# Main.net
KiCad netlist of a schematic drawn in Altium Designer
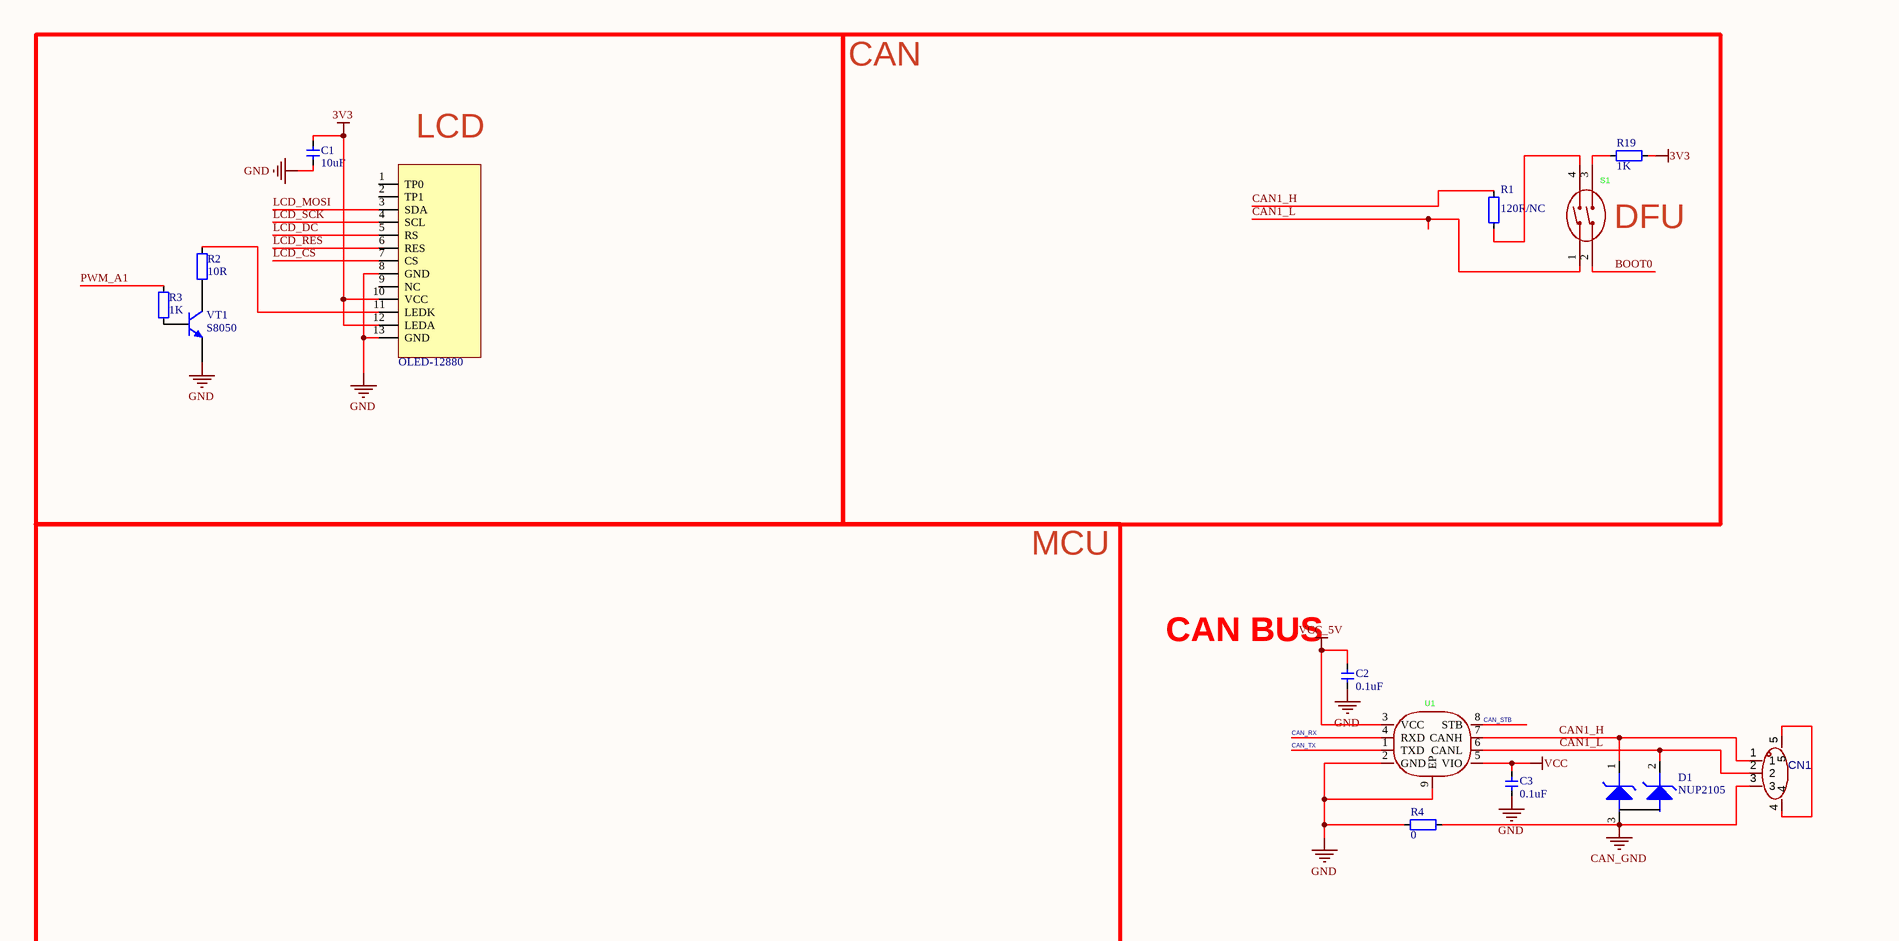
[diagram p0: Main.SchDoc, top]
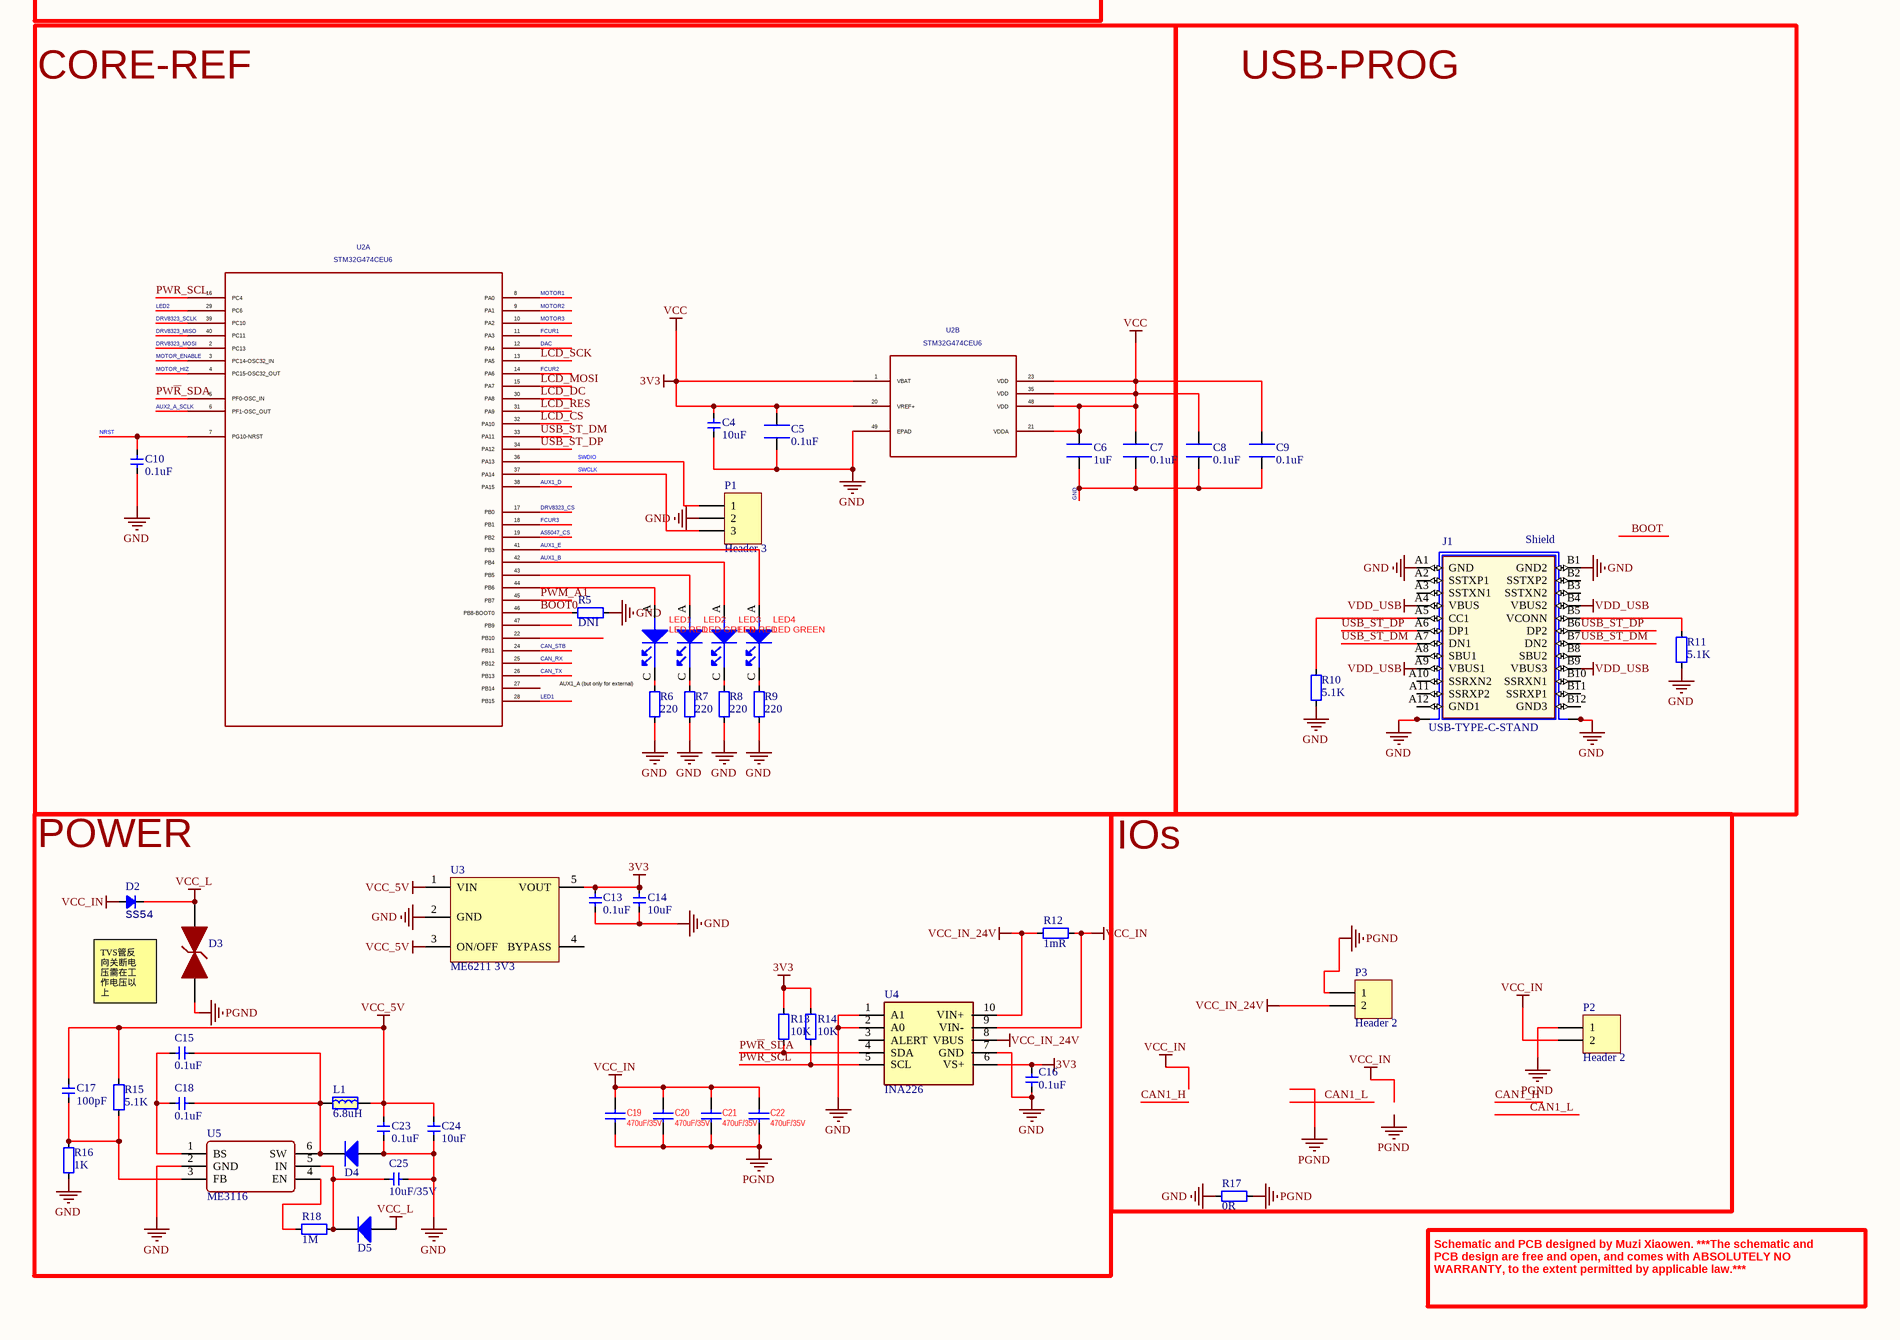
[diagram p1: Main.SchDoc, bottom]

(export (version "E")
  (design (tool "Eeschema 10.0.6"))
  (components
    (comp (ref "1")
      (value "OLED-12880")
      (footprint "OLED-12880")
      (libsource (lib "Schlib1") (part "LCD-ST7735"))
    )
    (comp (ref "C1")
      (value "10uF")
      (footprint "CAP_0402")
      (description "Capacitor")
      (libsource (lib "MyPcbLib") (part "电容-0402"))
    )
    (comp (ref "C2")
      (value "0.1uF")
      (footprint "CAP_0402")
      (description "Capacitor")
      (libsource (lib "MyPcbLib") (part "电容-0402"))
    )
    (comp (ref "C3")
      (value "0.1uF")
      (footprint "CAP_0402")
      (description "Capacitor")
      (libsource (lib "MyPcbLib") (part "电容-0402"))
    )
    (comp (ref "C4")
      (value "10uF")
      (footprint "CAP_0402")
      (description "Capacitor")
      (libsource (lib "MyPcbLib") (part "电容-0402"))
    )
    (comp (ref "C5")
      (value "0.1uF")
      (footprint "CAP_0402")
      (description "CAP CER 0.1UF 50V X7R 0603")
      (fields
        (field (name "MANUFACTURER") "Murata Electronics North America")
        (field (name "MANUFACTURER PART NUMBER") "GRM188R71H104KA93D")
      )
      (libsource (lib "CustomComponents") (part "GRM188R71H104KA93D"))
    )
    (comp (ref "C6")
      (value "1uF")
      (footprint "CAP_0402")
      (description "CAP CER 1UF 50V X7R 0603")
      (fields
        (field (name "MANUFACTURER") "Murata Electronics North America")
        (field (name "MANUFACTURER PART NUMBER") "GRM188R71H104KA93D")
      )
      (libsource (lib "CustomComponents") (part "GRM188R71H104KA93D"))
    )
    (comp (ref "C7")
      (value "0.1uF")
      (footprint "CAP_0402")
      (description "CAP CER 0.1UF 50V X7R 0603")
      (fields
        (field (name "MANUFACTURER") "Murata Electronics North America")
        (field (name "MANUFACTURER PART NUMBER") "GRM188R71H104KA93D")
      )
      (libsource (lib "CustomComponents") (part "GRM188R71H104KA93D"))
    )
    (comp (ref "C8")
      (value "0.1uF")
      (footprint "CAP_0402")
      (description "CAP CER 0.1UF 50V X7R 0603")
      (fields
        (field (name "MANUFACTURER") "Murata Electronics North America")
        (field (name "MANUFACTURER PART NUMBER") "GRM188R71H104KA93D")
      )
      (libsource (lib "CustomComponents") (part "GRM188R71H104KA93D"))
    )
    (comp (ref "C9")
      (value "0.1uF")
      (footprint "CAP_0402")
      (description "CAP CER 0.1UF 50V X7R 0603")
      (fields
        (field (name "MANUFACTURER") "Murata Electronics North America")
        (field (name "MANUFACTURER PART NUMBER") "GRM188R71H104KA93D")
      )
      (libsource (lib "CustomComponents") (part "GRM188R71H104KA93D"))
    )
    (comp (ref "C10")
      (value "0.1uF")
      (footprint "CAP_0402")
      (description "Capacitor")
      (libsource (lib "MyPcbLib") (part "电容-0402"))
    )
    (comp (ref "C13")
      (value "0.1uF")
      (footprint "CAP_0402")
      (description "Capacitor")
      (libsource (lib "MyPcbLib") (part "电容-0402"))
    )
    (comp (ref "C14")
      (value "10uF")
      (footprint "CAP_0402")
      (description "Capacitor")
      (libsource (lib "MyPcbLib") (part "电容-0402"))
    )
    (comp (ref "C15")
      (value "0.1uF")
      (footprint "CAP_0402")
      (description "Capacitor")
      (libsource (lib "MyPcbLib") (part "电容-0402"))
    )
    (comp (ref "C16")
      (value "0.1uF")
      (footprint "CAP_0402")
      (description "Capacitor")
      (libsource (lib "MyPcbLib") (part "电容-0402"))
    )
    (comp (ref "C17")
      (value "100pF")
      (footprint "CAP_0402")
      (description "Capacitor")
      (libsource (lib "MyPcbLib") (part "电容-0402"))
    )
    (comp (ref "C18")
      (value "0.1uF")
      (footprint "CAP_0402")
      (description "Capacitor")
      (libsource (lib "MyPcbLib") (part "电容-0402"))
    )
    (comp (ref "C19")
      (value "470uF/35V")
      (footprint "CAP-SMD_BD10.0-L10.3-W10.3-LS11.3-FD")
      (description "Capacitor, chip, ceramic")
      (fields (field (name "Comment") "220uF/25V"))
      (libsource (lib "OAKUSBFXS") (part "CAP"))
    )
    (comp (ref "C20")
      (value "470uF/35V")
      (footprint "CAP-SMD_BD10.0-L10.3-W10.3-LS11.3-FD")
      (description "Capacitor, chip, ceramic")
      (fields (field (name "Comment") "220uF/25V"))
      (libsource (lib "OAKUSBFXS") (part "CAP"))
    )
    (comp (ref "C21")
      (value "470uF/35V")
      (footprint "CAP-SMD_BD10.0-L10.3-W10.3-LS11.3-FD")
      (description "Capacitor, chip, ceramic")
      (fields (field (name "Comment") "220uF/25V"))
      (libsource (lib "OAKUSBFXS") (part "CAP"))
    )
    (comp (ref "C22")
      (value "470uF/35V")
      (footprint "CAP-SMD_BD10.0-L10.3-W10.3-LS11.3-FD")
      (description "Capacitor, chip, ceramic")
      (fields (field (name "Comment") "220uF/25V"))
      (libsource (lib "OAKUSBFXS") (part "CAP"))
    )
    (comp (ref "C23")
      (value "0.1uF")
      (footprint "CAP_0402")
      (description "Capacitor")
      (libsource (lib "MyPcbLib") (part "电容-0402"))
    )
    (comp (ref "C24")
      (value "10uF")
      (footprint "CAP_0402")
      (description "Capacitor")
      (libsource (lib "MyPcbLib") (part "电容-0402"))
    )
    (comp (ref "C25")
      (value "10uF/35V")
      (footprint "C0603")
      (description "Capacitor")
      (libsource (lib "MyPcbLib") (part "电容-0402"))
    )
    (comp (ref "CN1")
      (value "WAFER-GH1.25-3PLT-W1-P")
      (footprint "CONN-SMD_WAFER-GH1.25-3PLT-W1-P")
      (libsource (lib "altium-import") (part "root_0_WAFER-GH1.25-3PLT-W1-P_"))
    )
    (comp (ref "D1") (value "NUP2105") (footprint "SOT23-3") (libsource (lib "Schlib1") (part "NUP2105")))
    (comp (ref "D2")
      (value "SS54")
      (footprint "DO-214AC")
      (description "Diode")
      (libsource (lib "KitSprout") (part "Diode_SMA"))
    )
    (comp (ref "D3")
      (value "SMBJ28CA")
      (footprint "SMBJ-CA_MFG")
      (libsource (lib "MyPcbLib") (part "SMBJ28CA"))
    )
    (comp (ref "D4")
      (value "二极管-5819W")
      (footprint "SOD-323")
      (description "40V")
      (libsource (lib "MyPcbLib") (part "二极管-5819W"))
    )
    (comp (ref "D5")
      (value "二极管-5819W")
      (footprint "SOD-323")
      (description "40V")
      (libsource (lib "MyPcbLib") (part "二极管-5819W"))
    )
    (comp (ref "J1")
      (value "USB-TYPE-C-STAND")
      (footprint "USB-TYPE-C-STAND")
      (fields (field (name "MP") "632722110112") (field (name "MF") "Wurth Electronics"))
      (libsource (lib "MyPcbLib") (part "USB-TYPE-C-STAND"))
    )
    (comp (ref "L1") (value "6.8uH") (footprint "IND-201612") (libsource (lib "MyPcbLib") (part "电感-201612")))
    (comp (ref "LED1")
      (value "LED RED")
      (description "LED GRN SGL RA 25mA 4.1V SMD")
      (libsource (lib "*") (part "LED"))
    )
    (comp (ref "LED2")
      (value "LED GREEN")
      (description "LED GRN SGL RA 25mA 4.1V SMD")
      (libsource (lib "*") (part "LED"))
    )
    (comp (ref "LED3")
      (value "LED RED")
      (description "LED GRN SGL RA 25mA 4.1V SMD")
      (libsource (lib "*") (part "LED"))
    )
    (comp (ref "LED4")
      (value "LED GREEN")
      (description "LED GRN SGL RA 25mA 4.1V SMD")
      (libsource (lib "*") (part "LED"))
    )
    (comp (ref "P1")
      (value "Header 3")
      (footprint "HDR1X3")
      (description "Header, 3-Pin")
      (fields (field (name "PUBLISHER") "Altium Limited"))
      (libsource (lib "Miscellaneous Connectors") (part "Header 3"))
    )
    (comp (ref "P2")
      (value "Header 2")
      (footprint "CONN-TH_2P-P3.81_L7.4-W7.6")
      (description "Header, 2-Pin")
      (fields (field (name "PUBLISHER") "Altium Limited"))
      (libsource (lib "Miscellaneous Connectors") (part "Header 2"))
    )
    (comp (ref "P3")
      (value "Header 2")
      (footprint "CONN-TH_2P-P3.81_L7.4-W7.6")
      (description "Header, 2-Pin")
      (fields (field (name "PUBLISHER") "Altium Limited"))
      (libsource (lib "Miscellaneous Connectors") (part "Header 2"))
    )
    (comp (ref "R1")
      (value "120R/NC")
      (footprint "RES_0402_1")
      (description "Resistor")
      (libsource (lib "") (part "电阻-0402_2"))
    )
    (comp (ref "R2")
      (value "10R")
      (footprint "RES_0402_1")
      (description "Resistor")
      (libsource (lib "MyPcbLib") (part "电阻-0402"))
    )
    (comp (ref "R3")
      (value "1K")
      (footprint "RES_0402_1")
      (description "Resistor")
      (libsource (lib "") (part "电阻-0402_2"))
    )
    (comp (ref "R4")
      (value "0")
      (footprint "RES_0402")
      (description "Resistor")
      (libsource (lib "") (part "电阻-0402_1"))
    )
    (comp (ref "R5")
      (value "DNI")
      (footprint "RES_0402")
      (description "Resistor")
      (libsource (lib "") (part "电阻-0402_1"))
    )
    (comp (ref "R6")
      (value "220")
      (footprint "RES_0402_1")
      (description "Resistor")
      (libsource (lib "MyPcbLib") (part "电阻-0402"))
    )
    (comp (ref "R7")
      (value "220")
      (footprint "RES_0402_1")
      (description "Resistor")
      (libsource (lib "MyPcbLib") (part "电阻-0402"))
    )
    (comp (ref "R8")
      (value "220")
      (footprint "RES_0402_1")
      (description "Resistor")
      (libsource (lib "MyPcbLib") (part "电阻-0402"))
    )
    (comp (ref "R9")
      (value "220")
      (footprint "RES_0402_1")
      (description "Resistor")
      (libsource (lib "MyPcbLib") (part "电阻-0402"))
    )
    (comp (ref "R10")
      (value "5.1K")
      (footprint "RES_0402_1")
      (description "Resistor")
      (libsource (lib "") (part "电阻-0402_2"))
    )
    (comp (ref "R11")
      (value "5.1K")
      (footprint "RES_0402_1")
      (description "Resistor")
      (libsource (lib "") (part "电阻-0402_2"))
    )
    (comp (ref "R12")
      (value "1mR")
      (footprint "RES-SMD_L6.4-W3.2-R2512")
      (description "Resistor")
      (libsource (lib "MyPcbLib") (part "电阻-1206"))
    )
    (comp (ref "R13")
      (value "10K")
      (footprint "RES_0402_1")
      (description "Resistor")
      (libsource (lib "MyPcbLib") (part "电阻-0402"))
    )
    (comp (ref "R14")
      (value "10K")
      (footprint "RES_0402_1")
      (description "Resistor")
      (libsource (lib "MyPcbLib") (part "电阻-0402"))
    )
    (comp (ref "R15")
      (value "5.1K")
      (footprint "RES_0402_1")
      (description "Resistor")
      (libsource (lib "MyPcbLib") (part "电阻-0402"))
    )
    (comp (ref "R16")
      (value "1K")
      (footprint "RES_0402_1")
      (description "Resistor")
      (libsource (lib "MyPcbLib") (part "电阻-0402"))
    )
    (comp (ref "R17")
      (value "0R")
      (footprint "1206-RES")
      (description "Resistor")
      (libsource (lib "MyPcbLib") (part "电阻-1206"))
    )
    (comp (ref "R18")
      (value "1M")
      (footprint "RES_0402_1")
      (description "Resistor")
      (libsource (lib "") (part "电阻-0402_3"))
    )
    (comp (ref "R19")
      (value "1K")
      (footprint "RES_0402_1")
      (description "Resistor")
      (libsource (lib "") (part "电阻-0402_1"))
    )
    (comp (ref "S1")
      (value "ZX-1.27BM-2PSMD")
      (footprint "SW-SMD_2P-L5.4-W4.1-P1.27-LS8.4")
      (fields (field (name "MANUFACTURER") "Megastar(兆星)"))
      (libsource (lib "altium-import") (part "root_0_ZX-1.27BM-2PSMD_"))
    )
    (comp (ref "U1")
      (value "TCAN1057AVDRBRQ1")
      (footprint "SOIC8_2")
      (fields (field (name "MANUFACTURER") "SIT(芯力特)") (field (name "MANUFACTURER PART") "SIT1042ATK/3"))
      (libsource (lib "altium-import") (part "root_0_SIT1042ATK/3_"))
    )
    (comp (ref "U2")
      (value "STM32G474CEU6")
      (footprint "moteus:UFQFPN-48_7X7X0P55MM")
      (fields (field (name "MF") "ST") (field (name "Comment") "moteus_STM32G474CEU6"))
      (libsource (lib "altium-import") (part "root_0_moteus_STM32G474CEU6_"))
    )
    (comp (ref "U3")
      (value "ME6211 3V3")
      (footprint "SOT23-5")
      (description "LDO")
      (libsource (lib "MyPcbLib") (part "LP2992"))
    )
    (comp (ref "U4")
      (value "INA226")
      (footprint "MSOP-10_L3.0-W3.0-P0.50-LS5.0-BL")
      (fields
        (field (name "MOUSER PART NUMBER") "774-218-4LPSTJ")
        (field (name "MANUFACTURER_PART_NUMBER") "218-4LPSTJ")
      )
      (libsource (lib "Schlib1") (part "INA226"))
    )
    (comp (ref "U5")
      (value "ME3116")
      (footprint "SOT23-6")
      (description "DC-DC")
      (libsource (lib "MyPcbLib") (part "ME3116"))
    )
    (comp (ref "VT1")
      (value "S8050")
      (footprint "SMT_TRIODE_NPN")
      (description "Surface mount NPN transistor, package SOT-23")
      (libsource (lib "MyPcbLib") (part "SMT_TRIODE_NPN"))
    )
  )
  (nets
    (net (code "1") (name "/AS5047_CS") (class "Default")
      (node (ref "U2") (pin "19") (pinfunction "PB2_19") (pintype "passive"))
    )
    (net (code "2") (name "/AUX1_B") (class "Default")
      (node (ref "LED3") (pin "A") (pinfunction "ANODE_A") (pintype "passive"))
      (node (ref "U2") (pin "42") (pinfunction "PB4_42") (pintype "passive"))
    )
    (net (code "3") (name "/AUX1_D") (class "Default")
      (node (ref "U2") (pin "38") (pinfunction "PA15_38") (pintype "passive"))
    )
    (net (code "4") (name "/AUX1_E") (class "Default")
      (node (ref "LED4") (pin "A") (pinfunction "ANODE_A") (pintype "passive"))
      (node (ref "U2") (pin "41") (pinfunction "PB3_41") (pintype "passive"))
    )
    (net (code "5") (name "/AUX2_A_SCLK") (class "Default")
      (node (ref "U2") (pin "6") (pinfunction "PF1-OSC_OUT_6") (pintype "passive"))
    )
    (net (code "7") (name "/BOOT0") (class "Default")
      (node (ref "R5") (pin "1") (pinfunction "1_1") (pintype "passive"))
      (node (ref "S1") (pin "2") (pinfunction "2_2") (pintype "passive"))
      (node (ref "U2") (pin "46") (pinfunction "PB8-BOOT0_46") (pintype "passive"))
    )
    (net (code "8") (name "/CAN1_H") (class "Default")
      (node (ref "CN1") (pin "1") (pinfunction "1_1") (pintype "passive"))
      (node (ref "D1") (pin "1") (pinfunction "C_1") (pintype "passive"))
      (node (ref "R1") (pin "1") (pinfunction "1_1") (pintype "passive"))
      (node (ref "U1") (pin "7") (pinfunction "CANH_7") (pintype "passive"))
    )
    (net (code "9") (name "/CAN1_L") (class "Default")
      (node (ref "CN1") (pin "2") (pinfunction "2_2") (pintype "passive"))
      (node (ref "D1") (pin "2") (pinfunction "C_2") (pintype "passive"))
      (node (ref "S1") (pin "1") (pinfunction "1_1") (pintype "passive"))
      (node (ref "U1") (pin "6") (pinfunction "CANL_6") (pintype "passive"))
    )
    (net (code "10") (name "/CAN_RX") (class "Default")
      (node (ref "U1") (pin "4") (pinfunction "RXD_4") (pintype "passive"))
      (node (ref "U2") (pin "25") (pinfunction "PB12_25") (pintype "passive"))
    )
    (net (code "11") (name "/CAN_STB") (class "Default")
      (node (ref "U1") (pin "8") (pinfunction "STB_8") (pintype "passive"))
      (node (ref "U2") (pin "24") (pinfunction "PB11_24") (pintype "passive"))
    )
    (net (code "12") (name "/CAN_TX") (class "Default")
      (node (ref "U1") (pin "1") (pinfunction "TXD_1") (pintype "passive"))
      (node (ref "U2") (pin "26") (pinfunction "PB13_26") (pintype "passive"))
    )
    (net (code "13") (name "/DAC") (class "Default")
      (node (ref "U2") (pin "12") (pinfunction "PA4_12") (pintype "passive"))
    )
    (net (code "14") (name "/DRV8323_CS") (class "Default")
      (node (ref "U2") (pin "17") (pinfunction "PB0_17") (pintype "passive"))
    )
    (net (code "15") (name "/DRV8323_MISO") (class "Default")
      (node (ref "U2") (pin "40") (pinfunction "PC11_40") (pintype "passive"))
    )
    (net (code "16") (name "/DRV8323_MOSI") (class "Default")
      (node (ref "U2") (pin "2") (pinfunction "PC13_2") (pintype "passive"))
    )
    (net (code "17") (name "/DRV8323_SCLK") (class "Default")
      (node (ref "U2") (pin "39") (pinfunction "PC10_39") (pintype "passive"))
    )
    (net (code "18") (name "/FCUR1") (class "Default")
      (node (ref "U2") (pin "11") (pinfunction "PA3_11") (pintype "passive"))
    )
    (net (code "19") (name "/FCUR2") (class "Default")
      (node (ref "U2") (pin "14") (pinfunction "PA6_14") (pintype "passive"))
    )
    (net (code "20") (name "/FCUR3") (class "Default")
      (node (ref "U2") (pin "18") (pinfunction "PB1_18") (pintype "passive"))
    )
    (net (code "21") (name "/LCD_CS") (class "Default")
      (node (ref "1") (pin "7") (pinfunction "CS_7") (pintype "passive"))
      (node (ref "U2") (pin "32") (pinfunction "PA10_32") (pintype "passive"))
    )
    (net (code "22") (name "/LCD_DC") (class "Default")
      (node (ref "1") (pin "5") (pinfunction "RS_5") (pintype "passive"))
      (node (ref "U2") (pin "30") (pinfunction "PA8_30") (pintype "passive"))
    )
    (net (code "23") (name "/LCD_MOSI") (class "Default")
      (node (ref "1") (pin "3") (pinfunction "SDA_3") (pintype "passive"))
      (node (ref "U2") (pin "15") (pinfunction "PA7_15") (pintype "passive"))
    )
    (net (code "24") (name "/LCD_RES") (class "Default")
      (node (ref "1") (pin "6") (pinfunction "RES_6") (pintype "passive"))
      (node (ref "U2") (pin "31") (pinfunction "PA9_31") (pintype "passive"))
    )
    (net (code "25") (name "/LCD_SCK") (class "Default")
      (node (ref "1") (pin "4") (pinfunction "SCL_4") (pintype "passive"))
      (node (ref "U2") (pin "13") (pinfunction "PA5_13") (pintype "passive"))
    )
    (net (code "26") (name "/LED1") (class "Default")
      (node (ref "U2") (pin "28") (pinfunction "PB15_28") (pintype "passive"))
    )
    (net (code "27") (name "/LED2") (class "Default")
      (node (ref "U2") (pin "29") (pinfunction "PC6_29") (pintype "passive"))
    )
    (net (code "28") (name "/MOTOR1") (class "Default")
      (node (ref "U2") (pin "8") (pinfunction "PA0_8") (pintype "passive"))
    )
    (net (code "29") (name "/MOTOR2") (class "Default")
      (node (ref "U2") (pin "9") (pinfunction "PA1_9") (pintype "passive"))
    )
    (net (code "30") (name "/MOTOR3") (class "Default")
      (node (ref "U2") (pin "10") (pinfunction "PA2_10") (pintype "passive"))
    )
    (net (code "31") (name "/MOTOR_ENABLE") (class "Default")
      (node (ref "U2") (pin "3") (pinfunction "PC14-OSC32_IN_3") (pintype "passive"))
    )
    (net (code "32") (name "/MOTOR_HIZ") (class "Default")
      (node (ref "U2") (pin "4") (pinfunction "PC15-OSC32_OUT_4") (pintype "passive"))
    )
    (net (code "33") (name "/NRST") (class "Default")
      (node (ref "C10") (pin "2") (pinfunction "2_2") (pintype "passive"))
      (node (ref "U2") (pin "7") (pinfunction "PG10-NRST_7") (pintype "passive"))
    )
    (net (code "34") (name "/PWM_A1") (class "Default")
      (node (ref "R3") (pin "1") (pinfunction "1_1") (pintype "passive"))
      (node (ref "U2") (pin "45") (pinfunction "PB7_45") (pintype "passive"))
    )
    (net (code "35") (name "/PWR_SCL") (class "Default")
      (node (ref "R14") (pin "1") (pinfunction "1_1") (pintype "passive"))
      (node (ref "U2") (pin "16") (pinfunction "PC4_16") (pintype "passive"))
      (node (ref "U4") (pin "5") (pinfunction "SCL_5") (pintype "passive"))
    )
    (net (code "36") (name "/PW~{R}_SDA") (class "Default")
      (node (ref "R13") (pin "1") (pinfunction "1_1") (pintype "passive"))
      (node (ref "U2") (pin "5") (pinfunction "PF0-OSC_IN_5") (pintype "passive"))
      (node (ref "U4") (pin "4") (pinfunction "SDA_4") (pintype "passive"))
    )
    (net (code "37") (name "/SWCLK") (class "Default")
      (node (ref "P1") (pin "3") (pinfunction "3_3") (pintype "passive"))
      (node (ref "U2") (pin "37") (pinfunction "PA14_37") (pintype "passive"))
    )
    (net (code "38") (name "/SWDIO") (class "Default")
      (node (ref "P1") (pin "1") (pinfunction "1_1") (pintype "passive"))
      (node (ref "U2") (pin "36") (pinfunction "PA13_36") (pintype "passive"))
    )
    (net (code "39") (name "/USB_ST_DM") (class "Default")
      (node (ref "J1") (pin "A7") (pinfunction "DN1_A7") (pintype "bidirectional"))
      (node (ref "J1") (pin "B7") (pinfunction "DN2_B7") (pintype "bidirectional"))
      (node (ref "U2") (pin "33") (pinfunction "PA11_33") (pintype "passive"))
    )
    (net (code "40") (name "/USB_ST_DP") (class "Default")
      (node (ref "J1") (pin "A6") (pinfunction "DP1_A6") (pintype "bidirectional"))
      (node (ref "J1") (pin "B6") (pinfunction "DP2_B6") (pintype "bidirectional"))
      (node (ref "U2") (pin "34") (pinfunction "PA12_34") (pintype "passive"))
    )
    (net (code "41") (name "3V3") (class "Default")
      (node (ref "1") (pin "10") (pinfunction "VCC_10") (pintype "passive"))
      (node (ref "1") (pin "12") (pinfunction "LEDA_12") (pintype "passive"))
      (node (ref "C1") (pin "2") (pinfunction "2_2") (pintype "passive"))
      (node (ref "C13") (pin "2") (pinfunction "2_2") (pintype "passive"))
      (node (ref "C14") (pin "2") (pinfunction "2_2") (pintype "passive"))
      (node (ref "C16") (pin "2") (pinfunction "2_2") (pintype "passive"))
      (node (ref "C3") (pin "1") (pinfunction "1_1") (pintype "passive"))
      (node (ref "C4") (pin "2") (pinfunction "2_2") (pintype "passive"))
      (node (ref "C5") (pin "1") (pinfunction "1_1") (pintype "passive"))
      (node (ref "C6") (pin "1") (pinfunction "1_1") (pintype "passive"))
      (node (ref "C7") (pin "2") (pinfunction "2_2") (pintype "passive"))
      (node (ref "C8") (pin "1") (pinfunction "1_1") (pintype "passive"))
      (node (ref "C9") (pin "1") (pinfunction "1_1") (pintype "passive"))
      (node (ref "R13") (pin "2") (pinfunction "2_2") (pintype "passive"))
      (node (ref "R14") (pin "2") (pinfunction "2_2") (pintype "passive"))
      (node (ref "R19") (pin "2") (pinfunction "2_2") (pintype "passive"))
      (node (ref "U1") (pin "5") (pinfunction "VIO_5") (pintype "passive"))
      (node (ref "U2") (pin "1") (pinfunction "VBAT_1") (pintype "passive"))
      (node (ref "U2") (pin "20") (pinfunction "VREF+_20") (pintype "passive"))
      (node (ref "U2") (pin "21") (pinfunction "VDDA_21") (pintype "passive"))
      (node (ref "U2") (pin "23") (pinfunction "VDD_23") (pintype "passive"))
      (node (ref "U2") (pin "35") (pinfunction "VDD_35") (pintype "passive"))
      (node (ref "U2") (pin "48") (pinfunction "VDD_48") (pintype "passive"))
      (node (ref "U3") (pin "5") (pinfunction "VOUT_5") (pintype "passive"))
      (node (ref "U4") (pin "6") (pinfunction "VS+_6") (pintype "passive"))
    )
    (net (code "42") (name "CAN_GND") (class "Default")
      (node (ref "CN1") (pin "3") (pinfunction "3_3") (pintype "passive"))
      (node (ref "D1") (pin "3") (pinfunction "A_3") (pintype "passive"))
      (node (ref "R4") (pin "2") (pinfunction "2_2") (pintype "passive"))
    )
    (net (code "43") (name "GND") (class "Default")
      (node (ref "1") (pin "13") (pinfunction "GND_13") (pintype "passive"))
      (node (ref "1") (pin "8") (pinfunction "GND_8") (pintype "passive"))
      (node (ref "C1") (pin "1") (pinfunction "1_1") (pintype "passive"))
      (node (ref "C10") (pin "1") (pinfunction "1_1") (pintype "passive"))
      (node (ref "C13") (pin "1") (pinfunction "1_1") (pintype "passive"))
      (node (ref "C14") (pin "1") (pinfunction "1_1") (pintype "passive"))
      (node (ref "C16") (pin "1") (pinfunction "1_1") (pintype "passive"))
      (node (ref "C2") (pin "2") (pinfunction "2_2") (pintype "passive"))
      (node (ref "C23") (pin "1") (pinfunction "1_1") (pintype "passive"))
      (node (ref "C24") (pin "1") (pinfunction "1_1") (pintype "passive"))
      (node (ref "C25") (pin "2") (pinfunction "2_2") (pintype "passive"))
      (node (ref "C3") (pin "2") (pinfunction "2_2") (pintype "passive"))
      (node (ref "C4") (pin "1") (pinfunction "1_1") (pintype "passive"))
      (node (ref "C5") (pin "2") (pinfunction "2_2") (pintype "passive"))
      (node (ref "C6") (pin "2") (pinfunction "2_2") (pintype "passive"))
      (node (ref "C7") (pin "1") (pinfunction "1_1") (pintype "passive"))
      (node (ref "C8") (pin "2") (pinfunction "2_2") (pintype "passive"))
      (node (ref "C9") (pin "2") (pinfunction "2_2") (pintype "passive"))
      (node (ref "D4") (pin "1") (pinfunction "A_1") (pintype "passive"))
      (node (ref "J1") (pin "A1") (pinfunction "GND_A1") (pintype "bidirectional"))
      (node (ref "J1") (pin "B1") (pinfunction "GND2_B1") (pintype "bidirectional"))
      (node (ref "J1") (pin "S1") (pinfunction "SHIELD_S1") (pintype "bidirectional"))
      (node (ref "J1") (pin "S2") (pinfunction "SHIELD_S2") (pintype "bidirectional"))
      (node (ref "J1") (pin "S3") (pinfunction "SHIELD1_S3") (pintype "bidirectional"))
      (node (ref "J1") (pin "S4") (pinfunction "SHIELD1_S4") (pintype "bidirectional"))
      (node (ref "P1") (pin "2") (pinfunction "2_2") (pintype "passive"))
      (node (ref "R10") (pin "2") (pinfunction "2_2") (pintype "passive"))
      (node (ref "R11") (pin "2") (pinfunction "2_2") (pintype "passive"))
      (node (ref "R16") (pin "1") (pinfunction "1_1") (pintype "passive"))
      (node (ref "R17") (pin "1") (pinfunction "1_1") (pintype "passive"))
      (node (ref "R4") (pin "1") (pinfunction "1_1") (pintype "passive"))
      (node (ref "R5") (pin "2") (pinfunction "2_2") (pintype "passive"))
      (node (ref "R6") (pin "1") (pinfunction "1_1") (pintype "passive"))
      (node (ref "R7") (pin "1") (pinfunction "1_1") (pintype "passive"))
      (node (ref "R8") (pin "1") (pinfunction "1_1") (pintype "passive"))
      (node (ref "R9") (pin "1") (pinfunction "1_1") (pintype "passive"))
      (node (ref "U1") (pin "2") (pinfunction "GND_2") (pintype "passive"))
      (node (ref "U1") (pin "9") (pinfunction "EP_9") (pintype "passive"))
      (node (ref "U2") (pin "49") (pinfunction "EPAD_49") (pintype "passive"))
      (node (ref "U3") (pin "2") (pinfunction "GND_2") (pintype "passive"))
      (node (ref "U4") (pin "1") (pinfunction "A1_1") (pintype "passive"))
      (node (ref "U4") (pin "2") (pinfunction "A0_2") (pintype "passive"))
      (node (ref "U4") (pin "7") (pinfunction "GND_7") (pintype "passive"))
      (node (ref "U5") (pin "2") (pinfunction "GND_2") (pintype "passive"))
      (node (ref "VT1") (pin "2") (pinfunction "E_2") (pintype "passive"))
    )
    (net (code "44") (name "Net-(1-LEDK)") (class "Default")
      (node (ref "1") (pin "11") (pinfunction "LEDK_11") (pintype "passive"))
      (node (ref "R2") (pin "2") (pinfunction "2_2") (pintype "passive"))
    )
    (net (code "45") (name "Net-(CN1-Pad4)") (class "Default")
      (node (ref "CN1") (pin "4") (pinfunction "4_4") (pintype "passive"))
      (node (ref "CN1") (pin "5") (pinfunction "5_5") (pintype "passive"))
    )
    (net (code "46") (name "Net-(D4-K)") (class "Default")
      (node (ref "C15") (pin "1") (pinfunction "1_1") (pintype "passive"))
      (node (ref "C18") (pin "1") (pinfunction "1_1") (pintype "passive"))
      (node (ref "D4") (pin "2") (pinfunction "K_2") (pintype "passive"))
      (node (ref "L1") (pin "1") (pintype "passive"))
      (node (ref "U5") (pin "6") (pinfunction "SW_6") (pintype "passive"))
    )
    (net (code "47") (name "Net-(D5-K)") (class "Default")
      (node (ref "C25") (pin "1") (pinfunction "1_1") (pintype "passive"))
      (node (ref "D5") (pin "2") (pinfunction "K_2") (pintype "passive"))
      (node (ref "R18") (pin "1") (pinfunction "1_1") (pintype "passive"))
      (node (ref "U5") (pin "5") (pinfunction "IN_5") (pintype "passive"))
    )
    (net (code "48") (name "Net-(J1-CC1)") (class "Default")
      (node (ref "J1") (pin "A5") (pinfunction "CC1_A5") (pintype "bidirectional"))
      (node (ref "R10") (pin "1") (pinfunction "1_1") (pintype "passive"))
    )
    (net (code "49") (name "Net-(J1-VCONN)") (class "Default")
      (node (ref "J1") (pin "B5") (pinfunction "VCONN_B5") (pintype "bidirectional"))
      (node (ref "R11") (pin "1") (pinfunction "1_1") (pintype "passive"))
    )
    (net (code "50") (name "Net-(LED1-ANODE)") (class "Default")
      (node (ref "LED1") (pin "A") (pinfunction "ANODE_A") (pintype "passive"))
      (node (ref "U2") (pin "44") (pinfunction "PB6_44") (pintype "passive"))
    )
    (net (code "51") (name "Net-(LED1-CATHODE)") (class "Default")
      (node (ref "LED1") (pin "C") (pinfunction "CATHODE_C") (pintype "passive"))
      (node (ref "R6") (pin "2") (pinfunction "2_2") (pintype "passive"))
    )
    (net (code "52") (name "Net-(LED2-ANODE)") (class "Default")
      (node (ref "LED2") (pin "A") (pinfunction "ANODE_A") (pintype "passive"))
      (node (ref "U2") (pin "43") (pinfunction "PB5_43") (pintype "passive"))
    )
    (net (code "53") (name "Net-(LED2-CATHODE)") (class "Default")
      (node (ref "LED2") (pin "C") (pinfunction "CATHODE_C") (pintype "passive"))
      (node (ref "R7") (pin "2") (pinfunction "2_2") (pintype "passive"))
    )
    (net (code "54") (name "Net-(LED3-CATHODE)") (class "Default")
      (node (ref "LED3") (pin "C") (pinfunction "CATHODE_C") (pintype "passive"))
      (node (ref "R8") (pin "2") (pinfunction "2_2") (pintype "passive"))
    )
    (net (code "55") (name "Net-(LED4-CATHODE)") (class "Default")
      (node (ref "LED4") (pin "C") (pinfunction "CATHODE_C") (pintype "passive"))
      (node (ref "R9") (pin "2") (pinfunction "2_2") (pintype "passive"))
    )
    (net (code "56") (name "Net-(R1-Pad2)") (class "Default")
      (node (ref "R1") (pin "2") (pinfunction "2_2") (pintype "passive"))
      (node (ref "S1") (pin "4") (pinfunction "4_4") (pintype "passive"))
    )
    (net (code "57") (name "Net-(R19-Pad1)") (class "Default")
      (node (ref "R19") (pin "1") (pinfunction "1_1") (pintype "passive"))
      (node (ref "S1") (pin "3") (pinfunction "3_3") (pintype "passive"))
    )
    (net (code "58") (name "Net-(U5-BS)") (class "Default")
      (node (ref "C15") (pin "2") (pinfunction "2_2") (pintype "passive"))
      (node (ref "C18") (pin "2") (pinfunction "2_2") (pintype "passive"))
      (node (ref "U5") (pin "1") (pinfunction "BS_1") (pintype "passive"))
    )
    (net (code "59") (name "Net-(U5-EN)") (class "Default")
      (node (ref "R18") (pin "2") (pinfunction "2_2") (pintype "passive"))
      (node (ref "U5") (pin "4") (pinfunction "EN_4") (pintype "passive"))
    )
    (net (code "60") (name "Net-(U5-FB)") (class "Default")
      (node (ref "C17") (pin "2") (pinfunction "2_2") (pintype "passive"))
      (node (ref "R15") (pin "1") (pinfunction "1_1") (pintype "passive"))
      (node (ref "R16") (pin "2") (pinfunction "2_2") (pintype "passive"))
      (node (ref "U5") (pin "3") (pinfunction "FB_3") (pintype "passive"))
    )
    (net (code "61") (name "Net-(VT1-B)") (class "Default")
      (node (ref "R3") (pin "2") (pinfunction "2_2") (pintype "passive"))
      (node (ref "VT1") (pin "1") (pinfunction "B_1") (pintype "passive"))
    )
    (net (code "62") (name "Net-(VT1-C)") (class "Default")
      (node (ref "R2") (pin "1") (pinfunction "1_1") (pintype "passive"))
      (node (ref "VT1") (pin "3") (pinfunction "C_3") (pintype "passive"))
    )
    (net (code "63") (name "PGND") (class "Default")
      (node (ref "C19") (pin "2") (pinfunction "2_2") (pintype "passive"))
      (node (ref "C20") (pin "2") (pinfunction "2_2") (pintype "passive"))
      (node (ref "C21") (pin "2") (pinfunction "2_2") (pintype "passive"))
      (node (ref "C22") (pin "2") (pinfunction "2_2") (pintype "passive"))
      (node (ref "D3") (pin "1") (pinfunction "1_1") (pintype "passive"))
      (node (ref "P2") (pin "1") (pinfunction "1_1") (pintype "passive"))
      (node (ref "P3") (pin "1") (pinfunction "1_1") (pintype "passive"))
      (node (ref "R17") (pin "2") (pinfunction "2_2") (pintype "passive"))
    )
    (net (code "64") (name "VCC_5V") (class "Default")
      (node (ref "C17") (pin "1") (pinfunction "1_1") (pintype "passive"))
      (node (ref "C2") (pin "1") (pinfunction "1_1") (pintype "passive"))
      (node (ref "C23") (pin "2") (pinfunction "2_2") (pintype "passive"))
      (node (ref "C24") (pin "2") (pinfunction "2_2") (pintype "passive"))
      (node (ref "L1") (pin "2") (pinfunction "2_2") (pintype "passive"))
      (node (ref "R15") (pin "2") (pinfunction "2_2") (pintype "passive"))
      (node (ref "U1") (pin "3") (pinfunction "VCC_3") (pintype "passive"))
      (node (ref "U3") (pin "1") (pinfunction "VIN_1") (pintype "passive"))
      (node (ref "U3") (pin "3") (pinfunction "ON/OFF_3") (pintype "passive"))
    )
    (net (code "65") (name "VCC_IN") (class "Default")
      (node (ref "C19") (pin "1") (pinfunction "1_1") (pintype "passive"))
      (node (ref "C20") (pin "1") (pinfunction "1_1") (pintype "passive"))
      (node (ref "C21") (pin "1") (pinfunction "1_1") (pintype "passive"))
      (node (ref "C22") (pin "1") (pinfunction "1_1") (pintype "passive"))
      (node (ref "D2") (pin "1") (pinfunction "A_1") (pintype "passive"))
      (node (ref "P2") (pin "2") (pinfunction "2_2") (pintype "passive"))
      (node (ref "R12") (pin "2") (pinfunction "2_2") (pintype "passive"))
      (node (ref "U4") (pin "9") (pinfunction "VIN-_9") (pintype "passive"))
    )
    (net (code "66") (name "VCC_IN_24V") (class "Default")
      (node (ref "P3") (pin "2") (pinfunction "2_2") (pintype "passive"))
      (node (ref "R12") (pin "1") (pinfunction "1_1") (pintype "passive"))
      (node (ref "U4") (pin "10") (pinfunction "VIN+_10") (pintype "passive"))
      (node (ref "U4") (pin "8") (pinfunction "VBUS_8") (pintype "passive"))
    )
    (net (code "67") (name "VCC_L") (class "Default")
      (node (ref "D2") (pin "2") (pinfunction "K_2") (pintype "passive"))
      (node (ref "D3") (pin "2") (pinfunction "2_2") (pintype "passive"))
      (node (ref "D5") (pin "1") (pinfunction "A_1") (pintype "passive"))
    )
    (net (code "68") (name "VDD_USB") (class "Default")
      (node (ref "J1") (pin "A4") (pinfunction "VBUS_A4") (pintype "bidirectional"))
      (node (ref "J1") (pin "A9") (pinfunction "VBUS1_A9") (pintype "bidirectional"))
      (node (ref "J1") (pin "B4") (pinfunction "VBUS2_B4") (pintype "bidirectional"))
      (node (ref "J1") (pin "B9") (pinfunction "VBUS3_B9") (pintype "bidirectional"))
    )
    (net (code "69") (name "unconnected-(1-NC-Pad9)") (class "Default")
      (node (ref "1") (pin "9") (pinfunction "NC_9") (pintype "passive"))
    )
    (net (code "70") (name "unconnected-(1-TP0-Pad1)") (class "Default")
      (node (ref "1") (pin "1") (pinfunction "TP0_1") (pintype "passive"))
    )
    (net (code "71") (name "unconnected-(1-TP1-Pad2)") (class "Default")
      (node (ref "1") (pin "2") (pinfunction "TP1_2") (pintype "passive"))
    )
    (net (code "72") (name "unconnected-(J1-GND1-PadA12)") (class "Default")
      (node (ref "J1") (pin "A12") (pinfunction "GND1_A12") (pintype "bidirectional"))
    )
    (net (code "73") (name "unconnected-(J1-GND3-PadB12)") (class "Default")
      (node (ref "J1") (pin "B12") (pinfunction "GND3_B12") (pintype "bidirectional"))
    )
    (net (code "74") (name "unconnected-(J1-SBU1-PadA8)") (class "Default")
      (node (ref "J1") (pin "A8") (pinfunction "SBU1_A8") (pintype "bidirectional"))
    )
    (net (code "75") (name "unconnected-(J1-SBU2-PadB8)") (class "Default")
      (node (ref "J1") (pin "B8") (pinfunction "SBU2_B8") (pintype "bidirectional"))
    )
    (net (code "76") (name "unconnected-(J1-SSRXN1-PadB10)") (class "Default")
      (node (ref "J1") (pin "B10") (pinfunction "SSRXN1_B10") (pintype "bidirectional"))
    )
    (net (code "77") (name "unconnected-(J1-SSRXN2-PadA10)") (class "Default")
      (node (ref "J1") (pin "A10") (pinfunction "SSRXN2_A10") (pintype "bidirectional"))
    )
    (net (code "78") (name "unconnected-(J1-SSRXP1-PadB11)") (class "Default")
      (node (ref "J1") (pin "B11") (pinfunction "SSRXP1_B11") (pintype "bidirectional"))
    )
    (net (code "79") (name "unconnected-(J1-SSRXP2-PadA11)") (class "Default")
      (node (ref "J1") (pin "A11") (pinfunction "SSRXP2_A11") (pintype "bidirectional"))
    )
    (net (code "80") (name "unconnected-(J1-SSTXN1-PadA3)") (class "Default")
      (node (ref "J1") (pin "A3") (pinfunction "SSTXN1_A3") (pintype "bidirectional"))
    )
    (net (code "81") (name "unconnected-(J1-SSTXN2-PadB3)") (class "Default")
      (node (ref "J1") (pin "B3") (pinfunction "SSTXN2_B3") (pintype "bidirectional"))
    )
    (net (code "82") (name "unconnected-(J1-SSTXP1-PadA2)") (class "Default")
      (node (ref "J1") (pin "A2") (pinfunction "SSTXP1_A2") (pintype "bidirectional"))
    )
    (net (code "83") (name "unconnected-(J1-SSTXP2-PadB2)") (class "Default")
      (node (ref "J1") (pin "B2") (pinfunction "SSTXP2_B2") (pintype "bidirectional"))
    )
    (net (code "84") (name "unconnected-(U2A-PB9-Pad47)") (class "Default")
      (node (ref "U2") (pin "47") (pinfunction "PB9_47") (pintype "passive"))
    )
    (net (code "85") (name "unconnected-(U2A-PB10-Pad22)") (class "Default")
      (node (ref "U2") (pin "22") (pinfunction "PB10_22") (pintype "passive"))
    )
    (net (code "86") (name "unconnected-(U2A-PB14-Pad27)") (class "Default")
      (node (ref "U2") (pin "27") (pinfunction "PB14_27") (pintype "passive"))
    )
    (net (code "87") (name "unconnected-(U3-BYPASS-Pad4)") (class "Default")
      (node (ref "U3") (pin "4") (pinfunction "BYPASS_4") (pintype "passive"))
    )
    (net (code "88") (name "unconnected-(U4-ALERT-Pad3)") (class "Default")
      (node (ref "U4") (pin "3") (pinfunction "ALERT_3") (pintype "passive"))
    )
  )
)
